# 14_-_PWR_5V_3V3_2V5.net
KiCad netlist of a schematic drawn in Altium Designer
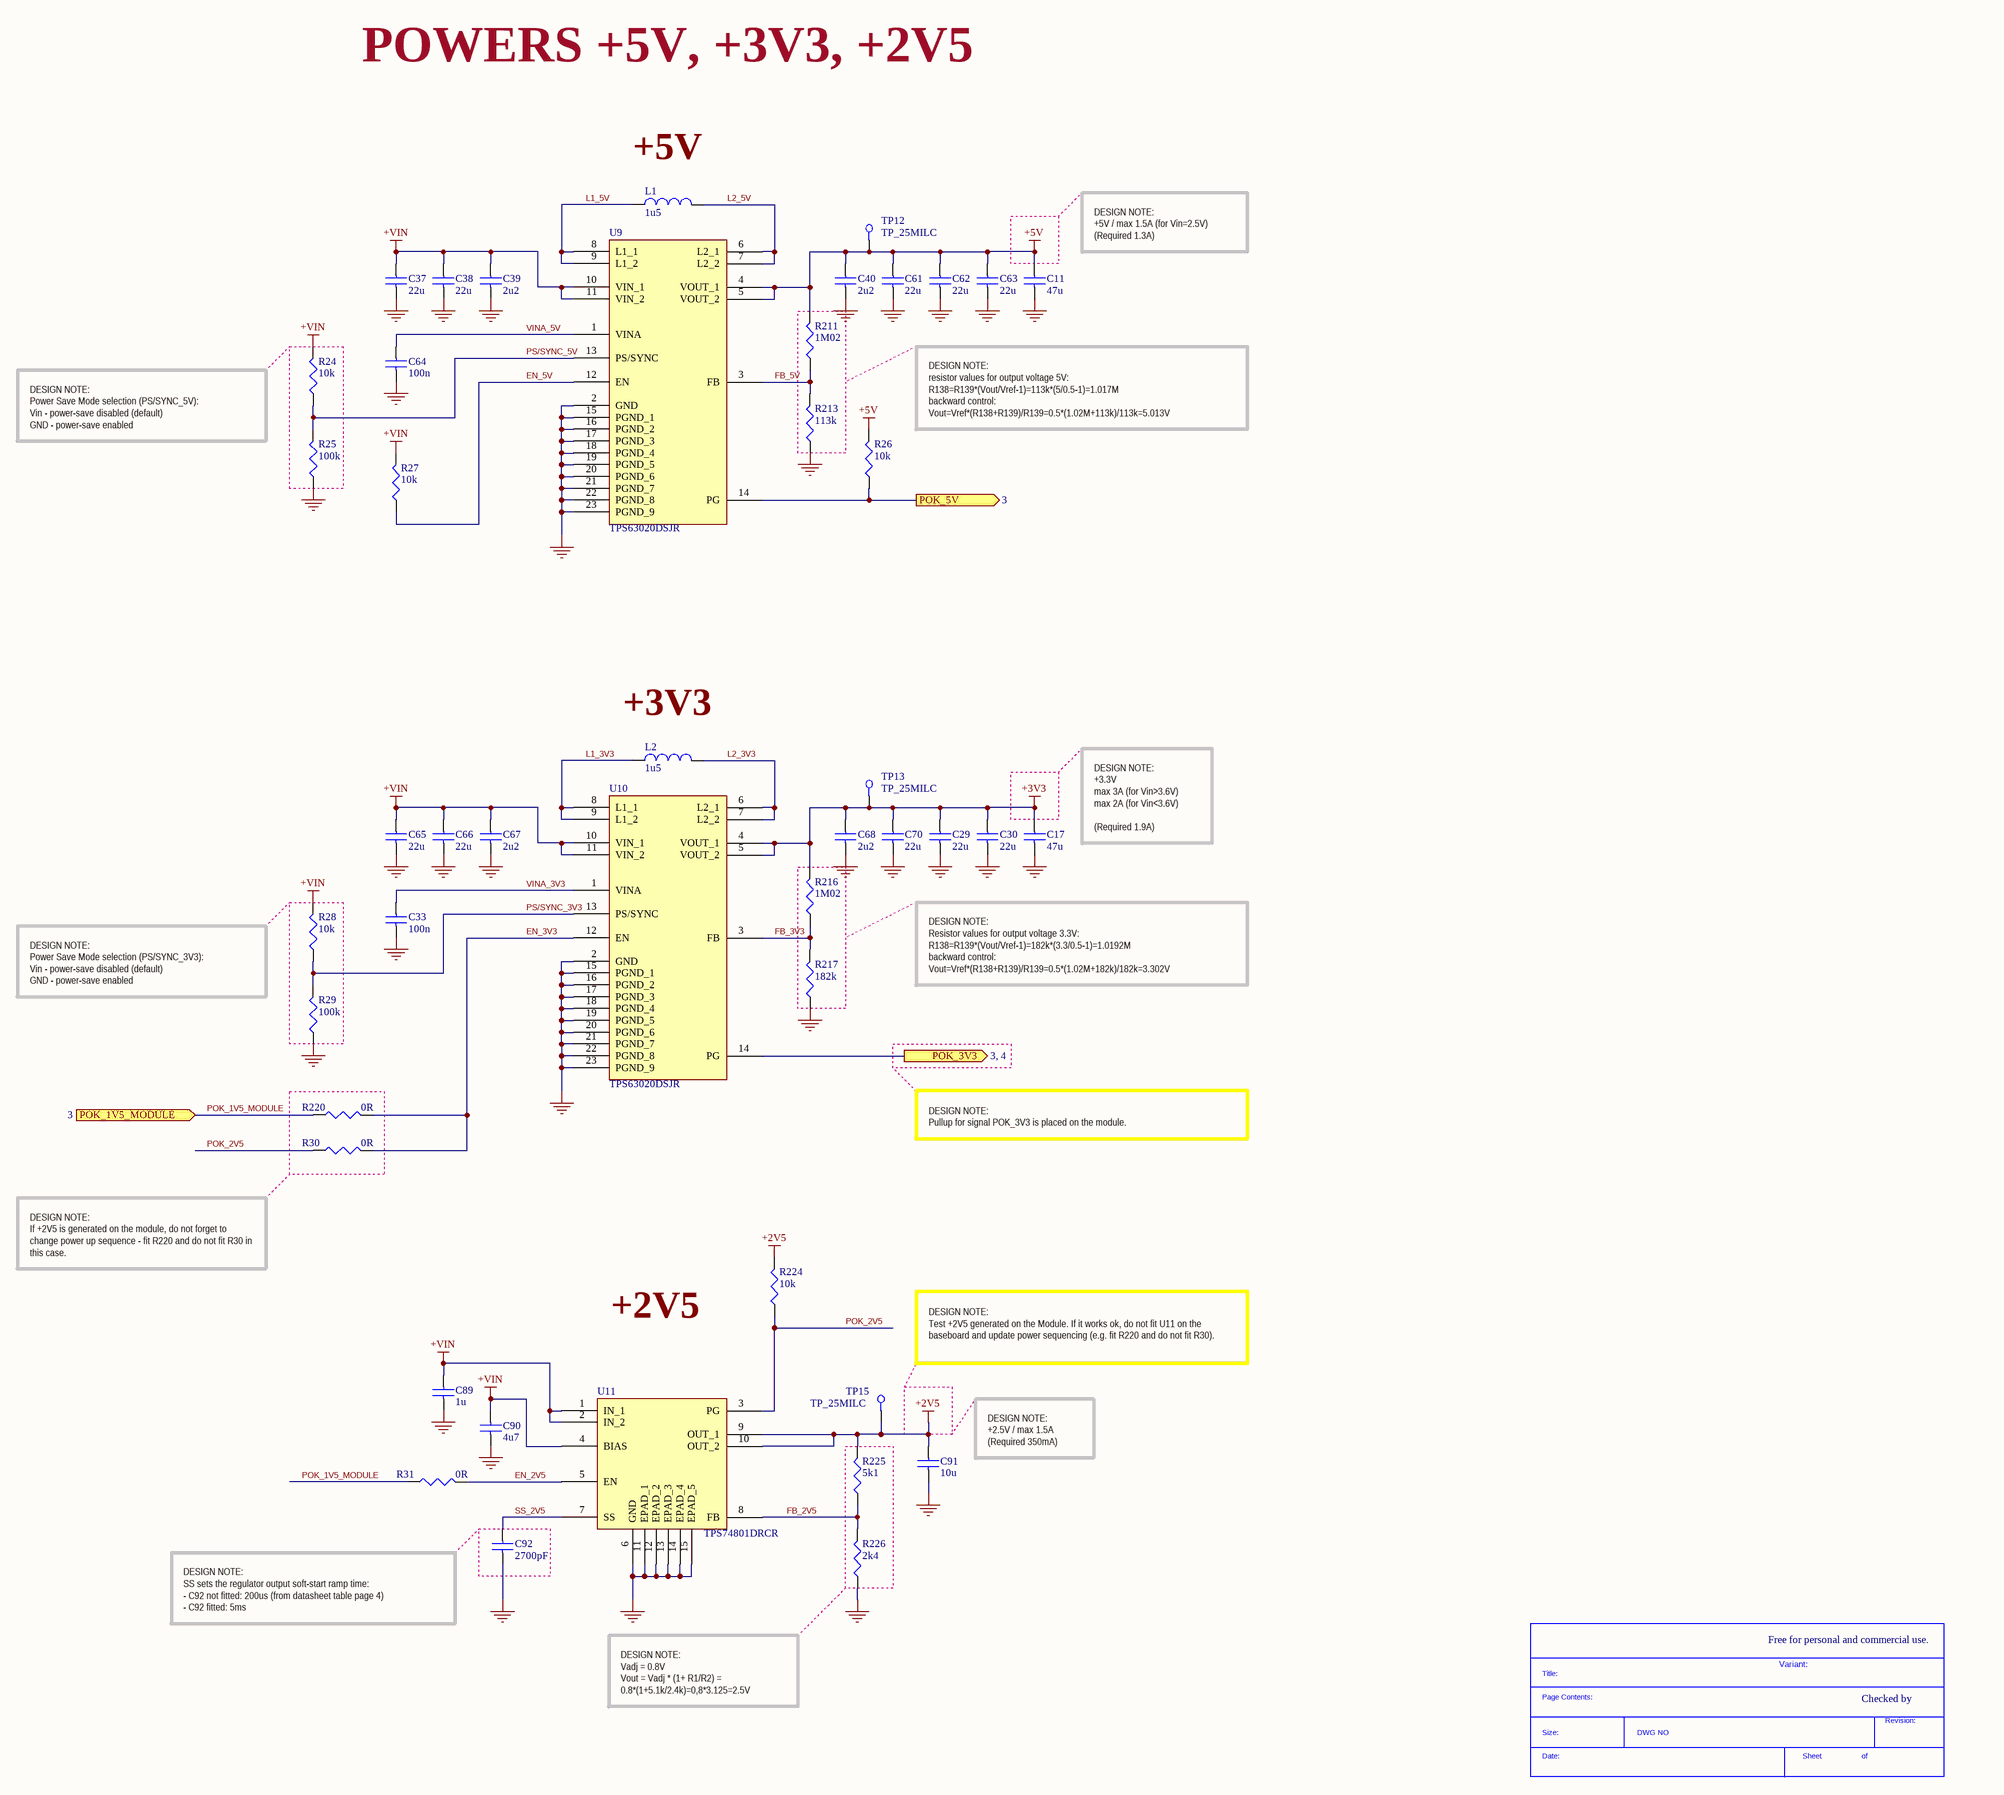
[diagram p0: [14] - PWR 5V, 3V3, 2V5.SchDoc]

(export (version "E")
  (design (tool "Eeschema 10.0.6"))
  (components
    (comp (ref "C11")
      (value "47u")
      (footprint "C0805")
      (description "CAP CER 47UF 6.3V 20% X5R 0805")
      (fields
        (field (name "MANUFACTURER") "Taiyo Yuden")
        (field (name "MANUFACTURER PART NUMBER") "JMK212BJ476MG-T")
        (field (name ".CREATOR") "MM")
        (field (name ".CHECKED SCH") "MM")
        (field (name ".CHECKED PCB") "MM")
      )
      (libsource (lib "Integrated_Library_FEDEVEL_APR_2015") (part "JMK212BJ476MG-T"))
    )
    (comp (ref "C17")
      (value "47u")
      (footprint "C0805")
      (description "CAP CER 47UF 6.3V 20% X5R 0805")
      (fields
        (field (name "MANUFACTURER") "Taiyo Yuden")
        (field (name "MANUFACTURER PART NUMBER") "JMK212BJ476MG-T")
        (field (name ".CREATOR") "MM")
        (field (name ".CHECKED SCH") "MM")
        (field (name ".CHECKED PCB") "MM")
      )
      (libsource (lib "Integrated_Library_FEDEVEL_APR_2015") (part "JMK212BJ476MG-T"))
    )
    (comp (ref "C29")
      (value "22u")
      (footprint "C0603")
      (description "CAP CER 22UF 6.3V 20% X5R 0603")
      (fields
        (field (name "MANUFACTURER") "TDK Corporation")
        (field (name "MANUFACTURER PART NUMBER") "C1608X5R0J226M080AC")
        (field (name ".CREATOR") "MM")
        (field (name ".CHECKED PCB") "MM")
        (field (name ".CHECKED SCH") "MM")
      )
      (libsource (lib "Integrated_Library_FEDEVEL_APR_2015") (part "C1608X5R0J226M080AC"))
    )
    (comp (ref "C30")
      (value "22u")
      (footprint "C0603")
      (description "CAP CER 22UF 6.3V 20% X5R 0603")
      (fields
        (field (name "MANUFACTURER") "TDK Corporation")
        (field (name "MANUFACTURER PART NUMBER") "C1608X5R0J226M080AC")
        (field (name ".CREATOR") "MM")
        (field (name ".CHECKED PCB") "MM")
        (field (name ".CHECKED SCH") "MM")
      )
      (libsource (lib "Integrated_Library_FEDEVEL_APR_2015") (part "C1608X5R0J226M080AC"))
    )
    (comp (ref "C33")
      (value "100n")
      (footprint "C0402")
      (description "CAP CER .10UF 50V X5R 10% 0402")
      (fields
        (field (name "MANUFACTURER") "TDK Corporation")
        (field (name "MANUFACTURER PART NUMBER") "C1005X5R1H104K")
      )
      (libsource (lib "Integrated_Library_FEDEVEL_APR_2015") (part "C1005X5R1H104K"))
    )
    (comp (ref "C37")
      (value "22u")
      (footprint "C0603")
      (description "CAP CER 22UF 6.3V 20% X5R 0603")
      (fields
        (field (name "MANUFACTURER") "TDK Corporation")
        (field (name "MANUFACTURER PART NUMBER") "C1608X5R0J226M080AC")
        (field (name ".CREATOR") "MM")
        (field (name ".CHECKED PCB") "MM")
        (field (name ".CHECKED SCH") "MM")
      )
      (libsource (lib "Integrated_Library_FEDEVEL_APR_2015") (part "C1608X5R0J226M080AC"))
    )
    (comp (ref "C38")
      (value "22u")
      (footprint "C0603")
      (description "CAP CER 22UF 6.3V 20% X5R 0603")
      (fields
        (field (name "MANUFACTURER") "TDK Corporation")
        (field (name "MANUFACTURER PART NUMBER") "C1608X5R0J226M080AC")
        (field (name ".CREATOR") "MM")
        (field (name ".CHECKED PCB") "MM")
        (field (name ".CHECKED SCH") "MM")
      )
      (libsource (lib "Integrated_Library_FEDEVEL_APR_2015") (part "C1608X5R0J226M080AC"))
    )
    (comp (ref "C39")
      (value "2u2")
      (footprint "C0402")
      (description "CAP CER 2.2UF 10V 10% X5R 0402")
      (fields
        (field (name "MANUFACTURER") "TDK Corporation")
        (field (name "MANUFACTURER PART NUMBER") "C1005X5R1A225K")
      )
      (libsource (lib "Integrated_Library_FEDEVEL_APR_2015") (part "C1005X5R1A225K"))
    )
    (comp (ref "C40")
      (value "2u2")
      (footprint "C0402")
      (description "CAP CER 2.2UF 10V 10% X5R 0402")
      (fields
        (field (name "MANUFACTURER") "TDK Corporation")
        (field (name "MANUFACTURER PART NUMBER") "C1005X5R1A225K")
      )
      (libsource (lib "Integrated_Library_FEDEVEL_APR_2015") (part "C1005X5R1A225K"))
    )
    (comp (ref "C61")
      (value "22u")
      (footprint "C0603")
      (description "CAP CER 22UF 6.3V 20% X5R 0603")
      (fields
        (field (name "MANUFACTURER") "TDK Corporation")
        (field (name "MANUFACTURER PART NUMBER") "C1608X5R0J226M080AC")
        (field (name ".CREATOR") "MM")
        (field (name ".CHECKED PCB") "MM")
        (field (name ".CHECKED SCH") "MM")
      )
      (libsource (lib "Integrated_Library_FEDEVEL_APR_2015") (part "C1608X5R0J226M080AC"))
    )
    (comp (ref "C62")
      (value "22u")
      (footprint "C0603")
      (description "CAP CER 22UF 6.3V 20% X5R 0603")
      (fields
        (field (name "MANUFACTURER") "TDK Corporation")
        (field (name "MANUFACTURER PART NUMBER") "C1608X5R0J226M080AC")
        (field (name ".CREATOR") "MM")
        (field (name ".CHECKED PCB") "MM")
        (field (name ".CHECKED SCH") "MM")
      )
      (libsource (lib "Integrated_Library_FEDEVEL_APR_2015") (part "C1608X5R0J226M080AC"))
    )
    (comp (ref "C63")
      (value "22u")
      (footprint "C0603")
      (description "CAP CER 22UF 6.3V 20% X5R 0603")
      (fields
        (field (name "MANUFACTURER") "TDK Corporation")
        (field (name "MANUFACTURER PART NUMBER") "C1608X5R0J226M080AC")
        (field (name ".CREATOR") "MM")
        (field (name ".CHECKED PCB") "MM")
        (field (name ".CHECKED SCH") "MM")
      )
      (libsource (lib "Integrated_Library_FEDEVEL_APR_2015") (part "C1608X5R0J226M080AC"))
    )
    (comp (ref "C64")
      (value "100n")
      (footprint "C0402")
      (description "CAP CER .10UF 50V X5R 10% 0402")
      (fields
        (field (name "MANUFACTURER") "TDK Corporation")
        (field (name "MANUFACTURER PART NUMBER") "C1005X5R1H104K")
      )
      (libsource (lib "Integrated_Library_FEDEVEL_APR_2015") (part "C1005X5R1H104K"))
    )
    (comp (ref "C65")
      (value "22u")
      (footprint "C0603")
      (description "CAP CER 22UF 6.3V 20% X5R 0603")
      (fields
        (field (name "MANUFACTURER") "TDK Corporation")
        (field (name "MANUFACTURER PART NUMBER") "C1608X5R0J226M080AC")
        (field (name ".CREATOR") "MM")
        (field (name ".CHECKED PCB") "MM")
        (field (name ".CHECKED SCH") "MM")
      )
      (libsource (lib "Integrated_Library_FEDEVEL_APR_2015") (part "C1608X5R0J226M080AC"))
    )
    (comp (ref "C66")
      (value "22u")
      (footprint "C0603")
      (description "CAP CER 22UF 6.3V 20% X5R 0603")
      (fields
        (field (name "MANUFACTURER") "TDK Corporation")
        (field (name "MANUFACTURER PART NUMBER") "C1608X5R0J226M080AC")
        (field (name ".CREATOR") "MM")
        (field (name ".CHECKED PCB") "MM")
        (field (name ".CHECKED SCH") "MM")
      )
      (libsource (lib "Integrated_Library_FEDEVEL_APR_2015") (part "C1608X5R0J226M080AC"))
    )
    (comp (ref "C67")
      (value "2u2")
      (footprint "C0402")
      (description "CAP CER 2.2UF 10V 10% X5R 0402")
      (fields
        (field (name "MANUFACTURER") "TDK Corporation")
        (field (name "MANUFACTURER PART NUMBER") "C1005X5R1A225K")
      )
      (libsource (lib "Integrated_Library_FEDEVEL_APR_2015") (part "C1005X5R1A225K"))
    )
    (comp (ref "C68")
      (value "2u2")
      (footprint "C0402")
      (description "CAP CER 2.2UF 10V 10% X5R 0402")
      (fields
        (field (name "MANUFACTURER") "TDK Corporation")
        (field (name "MANUFACTURER PART NUMBER") "C1005X5R1A225K")
      )
      (libsource (lib "Integrated_Library_FEDEVEL_APR_2015") (part "C1005X5R1A225K"))
    )
    (comp (ref "C70")
      (value "22u")
      (footprint "C0603")
      (description "CAP CER 22UF 6.3V 20% X5R 0603")
      (fields
        (field (name "MANUFACTURER") "TDK Corporation")
        (field (name "MANUFACTURER PART NUMBER") "C1608X5R0J226M080AC")
        (field (name ".CREATOR") "MM")
        (field (name ".CHECKED PCB") "MM")
        (field (name ".CHECKED SCH") "MM")
      )
      (libsource (lib "Integrated_Library_FEDEVEL_APR_2015") (part "C1608X5R0J226M080AC"))
    )
    (comp (ref "C89")
      (value "1u")
      (footprint "C0402")
      (description "CAP CER 1.0UF 16V X5R 0402")
      (fields
        (field (name "MANUFACTURER") "TDK Corporation")
        (field (name "MANUFACTURER PART NUMBER") "C1005X5R1C105K")
      )
      (libsource (lib "Integrated_Library_FEDEVEL_APR_2015") (part "C1005X5R1C105K"))
    )
    (comp (ref "C90")
      (value "4u7")
      (footprint "C0402")
      (description "CAP CER 4.7UF 10V 20% X5R 0402")
      (fields
        (field (name "MANUFACTURER") "TDK Corporation")
        (field (name "MANUFACTURER PART NUMBER") "C1005X5R1A475M")
      )
      (libsource (lib "Integrated_Library_FEDEVEL_APR_2015") (part "C1005X5R1A475M"))
    )
    (comp (ref "C91")
      (value "10u")
      (footprint "C0603")
      (description "CAP CER 10UF 6.3V X5R 20% 0603")
      (fields
        (field (name "MANUFACTURER") "TDK Corporation")
        (field (name "MANUFACTURER PART NUMBER") "C1608X5R0J106M")
      )
      (libsource (lib "Integrated_Library_FEDEVEL_APR_2015") (part "C1608X5R0J106M"))
    )
    (comp (ref "C92")
      (value "2700pF")
      (footprint "C0402")
      (description "CAP CER 2700PF 50V 10% X7R 0402")
      (fields
        (field (name "MANUFACTURER") "Murata Electronics North America")
        (field (name "MANUFACTURER PART NUMBER") "GRM155R71H272KA01D")
      )
      (libsource (lib "Integrated_Library_FEDEVEL_APR_2015") (part "GRM155R71H272KA01D"))
    )
    (comp (ref "L1")
      (value "1u5")
      (footprint "IHLP_204MILX216MIL")
      (description "FIXED IND 1.5UH 7.5A 18.5 MOHM")
      (fields
        (field (name "MANUFACTURER") "Vishay Dale")
        (field (name "MANUFACTURER PART NUMBER") "IHLP2020CZER1R5M11")
        (field (name ".CREATOR") "MM")
        (field (name ".CHECKED PCB") "MM")
        (field (name ".CHECKED SCH") "MM")
      )
      (libsource (lib "Integrated_Library_FEDEVEL_APR_2015") (part "IHLP2020CZER1R5M11"))
    )
    (comp (ref "L2")
      (value "1u5")
      (footprint "IHLP_204MILX216MIL")
      (description "FIXED IND 1.5UH 7.5A 18.5 MOHM")
      (fields
        (field (name "MANUFACTURER") "Vishay Dale")
        (field (name "MANUFACTURER PART NUMBER") "IHLP2020CZER1R5M11")
        (field (name ".CREATOR") "MM")
        (field (name ".CHECKED PCB") "MM")
        (field (name ".CHECKED SCH") "MM")
      )
      (libsource (lib "Integrated_Library_FEDEVEL_APR_2015") (part "IHLP2020CZER1R5M11"))
    )
    (comp (ref "R24")
      (value "10k")
      (footprint "R0402")
      (description "RES 10.0K OHM 1/16W 1% 0402 SMD")
      (fields
        (field (name "MANUFACTURER") "Yageo")
        (field (name "MANUFACTURER PART NUMBER") "RC0402FR-0710KL")
      )
      (libsource (lib "Integrated_Library_FEDEVEL_APR_2015") (part "RC0402FR-0710KL"))
    )
    (comp (ref "R25")
      (value "100k")
      (footprint "R0402")
      (description "RES 100K OHM 1/16W 1% 0402 SMD")
      (fields
        (field (name "MANUFACTURER") "Stackpole Electronics Inc")
        (field (name "MANUFACTURER PART NUMBER") "RMCF0402FT100K")
      )
      (libsource (lib "Integrated_Library_FEDEVEL_APR_2015") (part "RMCF0402FT100K"))
    )
    (comp (ref "R26")
      (value "10k")
      (footprint "R0402")
      (description "RES 10.0K OHM 1/16W 1% 0402 SMD")
      (fields
        (field (name "MANUFACTURER") "Yageo")
        (field (name "MANUFACTURER PART NUMBER") "RC0402FR-0710KL")
      )
      (libsource (lib "Integrated_Library_FEDEVEL_APR_2015") (part "RC0402FR-0710KL"))
    )
    (comp (ref "R27")
      (value "10k")
      (footprint "R0402")
      (description "RES 10.0K OHM 1/16W 1% 0402 SMD")
      (fields
        (field (name "MANUFACTURER") "Yageo")
        (field (name "MANUFACTURER PART NUMBER") "RC0402FR-0710KL")
      )
      (libsource (lib "Integrated_Library_FEDEVEL_APR_2015") (part "RC0402FR-0710KL"))
    )
    (comp (ref "R28")
      (value "10k")
      (footprint "R0402")
      (description "RES 10.0K OHM 1/16W 1% 0402 SMD")
      (fields
        (field (name "MANUFACTURER") "Yageo")
        (field (name "MANUFACTURER PART NUMBER") "RC0402FR-0710KL")
      )
      (libsource (lib "Integrated_Library_FEDEVEL_APR_2015") (part "RC0402FR-0710KL"))
    )
    (comp (ref "R29")
      (value "100k")
      (footprint "R0402")
      (description "RES 100K OHM 1/16W 1% 0402 SMD")
      (fields
        (field (name "MANUFACTURER") "Stackpole Electronics Inc")
        (field (name "MANUFACTURER PART NUMBER") "RMCF0402FT100K")
      )
      (libsource (lib "Integrated_Library_FEDEVEL_APR_2015") (part "RMCF0402FT100K"))
    )
    (comp (ref "R30")
      (value "0R")
      (footprint "R0402")
      (description "RES 0.0 OHM 1/16W 0402 SMD")
      (fields
        (field (name "MANUFACTURER") "Yageo")
        (field (name "MANUFACTURER PART NUMBER") "RC0402JR-070RL")
      )
      (libsource (lib "Integrated_Library_FEDEVEL_APR_2015") (part "RC0402JR-070RL"))
    )
    (comp (ref "R31")
      (value "0R")
      (footprint "R0402")
      (description "RES 0.0 OHM 1/16W 0402 SMD")
      (fields
        (field (name "MANUFACTURER") "Yageo")
        (field (name "MANUFACTURER PART NUMBER") "RC0402JR-070RL")
      )
      (libsource (lib "Integrated_Library_FEDEVEL_APR_2015") (part "RC0402JR-070RL"))
    )
    (comp (ref "R211")
      (value "1M02")
      (footprint "R0402")
      (description "RES 1.02M OHM 1/16W 1% 0402 SMD")
      (fields
        (field (name "MANUFACTURER") "Vishay Dale")
        (field (name "MANUFACTURER PART NUMBER") "CRCW04021M02FKED")
        (field (name ".CREATOR") "MM")
        (field (name ".CHECKED PCB") "MM")
        (field (name ".CHECKED SCH") "MM")
      )
      (libsource (lib "Integrated_Library_FEDEVEL_APR_2015") (part "CRCW04021M02FKED"))
    )
    (comp (ref "R213")
      (value "113k")
      (footprint "R0402")
      (description "RES 113K OHM 1/16W 1% 0402 SMD")
      (fields
        (field (name "MANUFACTURER") "Vishay Dale")
        (field (name "MANUFACTURER PART NUMBER") "CRCW0402113KFKED")
        (field (name ".CREATOR") "MM")
        (field (name ".CHECKED PCB") "MM")
        (field (name ".CHECKED SCH") "MM")
      )
      (libsource (lib "Integrated_Library_FEDEVEL_APR_2015") (part "CRCW0402113KFKED"))
    )
    (comp (ref "R216")
      (value "1M02")
      (footprint "R0402")
      (description "RES 1.02M OHM 1/16W 1% 0402 SMD")
      (fields
        (field (name "MANUFACTURER") "Vishay Dale")
        (field (name "MANUFACTURER PART NUMBER") "CRCW04021M02FKED")
        (field (name ".CREATOR") "MM")
        (field (name ".CHECKED PCB") "MM")
        (field (name ".CHECKED SCH") "MM")
      )
      (libsource (lib "Integrated_Library_FEDEVEL_APR_2015") (part "CRCW04021M02FKED"))
    )
    (comp (ref "R217")
      (value "182k")
      (footprint "R0402")
      (description "RES 182K OHM 1/16W 1% 0402 SMD")
      (fields
        (field (name "MANUFACTURER") "Vishay Dale")
        (field (name "MANUFACTURER PART NUMBER") "CRCW0402182KFKED")
        (field (name ".CREATOR") "MM")
        (field (name ".CHECKED PCB") "MM")
        (field (name ".CHECKED SCH") "MM")
      )
      (libsource (lib "Integrated_Library_FEDEVEL_APR_2015") (part "CRCW0402182KFKED"))
    )
    (comp (ref "R220")
      (value "0R")
      (footprint "R0402")
      (description "RES 0.0 OHM 1/16W 0402 SMD")
      (fields
        (field (name "MANUFACTURER") "Yageo")
        (field (name "MANUFACTURER PART NUMBER") "RC0402JR-070RL")
      )
      (libsource (lib "Integrated_Library_FEDEVEL_APR_2015") (part "RC0402JR-070RL"))
    )
    (comp (ref "R224")
      (value "10k")
      (footprint "R0402")
      (description "RES 10.0K OHM 1/16W 1% 0402 SMD")
      (fields
        (field (name "MANUFACTURER") "Yageo")
        (field (name "MANUFACTURER PART NUMBER") "RC0402FR-0710KL")
      )
      (libsource (lib "Integrated_Library_FEDEVEL_APR_2015") (part "RC0402FR-0710KL"))
    )
    (comp (ref "R225")
      (value "5k1")
      (footprint "R0402")
      (description "RES 5.10K OHM 1/16W 1% 0402 SMD")
      (fields
        (field (name "MANUFACTURER") "Yageo")
        (field (name "MANUFACTURER PART NUMBER") "RC0402FR-075K1L")
        (field (name ".CHECKED PCB") "RF")
        (field (name ".CHECKED SCH") "RF")
      )
      (libsource (lib "Integrated_Library_FEDEVEL_APR_2015") (part "RC0402FR-075K1L"))
    )
    (comp (ref "R226")
      (value "2k4")
      (footprint "R0402")
      (description "RES 2.40K OHM 1/16W 1% 0402 SMD")
      (fields
        (field (name "MANUFACTURER") "Vishay Dale")
        (field (name "MANUFACTURER PART NUMBER") "CRCW04022K40FKED")
      )
      (libsource (lib "Integrated_Library_FEDEVEL_APR_2015") (part "CRCW04022K40FKED"))
    )
    (comp (ref "TP12")
      (value "TP_25MILC")
      (footprint "TP_25C")
      (description "Test Point 25mil")
      (libsource (lib "Integrated_Library_FEDEVEL_APR_2015") (part "TP_25MILC"))
    )
    (comp (ref "TP13")
      (value "TP_25MILC")
      (footprint "TP_25C")
      (description "Test Point 25mil")
      (libsource (lib "Integrated_Library_FEDEVEL_APR_2015") (part "TP_25MILC"))
    )
    (comp (ref "TP15")
      (value "TP_25MILC")
      (footprint "TP_25C")
      (description "Test Point 25mil")
      (libsource (lib "Integrated_Library_FEDEVEL_APR_2015") (part "TP_25MILC"))
    )
    (comp (ref "U9")
      (value "TPS63020DSJR")
      (footprint "DSJ (R-PVSON-N14)")
      (description "IC REG BUCK BST SYNC ADJ 14VSON")
      (fields
        (field (name "MANUFACTURER") "Texas Instruments")
        (field (name ".CREATOR") "MM")
        (field (name ".CHECKED PCB") "MM")
        (field (name ".CHECKED SCH") "MM")
      )
      (libsource (lib "Integrated_Library_FEDEVEL_APR_2015") (part "TPS63020DSJR"))
    )
    (comp (ref "U10")
      (value "TPS63020DSJR")
      (footprint "DSJ (R-PVSON-N14)")
      (description "IC REG BUCK BST SYNC ADJ 14VSON")
      (fields
        (field (name "MANUFACTURER") "Texas Instruments")
        (field (name ".CREATOR") "MM")
        (field (name ".CHECKED PCB") "MM")
        (field (name ".CHECKED SCH") "MM")
      )
      (libsource (lib "Integrated_Library_FEDEVEL_APR_2015") (part "TPS63020DSJR"))
    )
    (comp (ref "U11")
      (value "TPS74801DRCR")
      (footprint "DRC (S-PVSON-N10)")
      (description "IC REG LDO ADJ 1.5A 10SON")
      (fields (field (name "MANUFACTURER") "Texas Instruments") (field (name ".CREATOR") "MM"))
      (libsource (lib "Integrated_Library_FEDEVEL_APR_2015") (part "TPS74801DRCR"))
    )
  )
  (nets
    (net (code "1") (name "+2V5") (class "Default")
      (node (ref "C91") (pin "1") (pinfunction "1_1") (pintype "passive"))
      (node (ref "R224") (pin "2") (pinfunction "2_2") (pintype "passive"))
      (node (ref "R225") (pin "2") (pinfunction "2_2") (pintype "passive"))
      (node (ref "TP15") (pin "1") (pinfunction "1_1") (pintype "passive"))
      (node (ref "U11") (pin "10") (pinfunction "OUT_2_10") (pintype "passive"))
      (node (ref "U11") (pin "9") (pinfunction "OUT_1_9") (pintype "passive"))
    )
    (net (code "2") (name "+3V3") (class "Default")
      (node (ref "C17") (pin "1") (pinfunction "1_1") (pintype "passive"))
      (node (ref "C29") (pin "1") (pinfunction "1_1") (pintype "passive"))
      (node (ref "C30") (pin "1") (pinfunction "1_1") (pintype "passive"))
      (node (ref "C68") (pin "1") (pinfunction "1_1") (pintype "passive"))
      (node (ref "C70") (pin "1") (pinfunction "1_1") (pintype "passive"))
      (node (ref "R216") (pin "2") (pinfunction "2_2") (pintype "passive"))
      (node (ref "TP13") (pin "1") (pinfunction "1_1") (pintype "passive"))
      (node (ref "U10") (pin "4") (pinfunction "VOUT_1_4") (pintype "passive"))
      (node (ref "U10") (pin "5") (pinfunction "VOUT_2_5") (pintype "passive"))
    )
    (net (code "3") (name "+5V") (class "Default")
      (node (ref "C11") (pin "1") (pinfunction "1_1") (pintype "passive"))
      (node (ref "C40") (pin "1") (pinfunction "1_1") (pintype "passive"))
      (node (ref "C61") (pin "1") (pinfunction "1_1") (pintype "passive"))
      (node (ref "C62") (pin "1") (pinfunction "1_1") (pintype "passive"))
      (node (ref "C63") (pin "1") (pinfunction "1_1") (pintype "passive"))
      (node (ref "R211") (pin "2") (pinfunction "2_2") (pintype "passive"))
      (node (ref "R26") (pin "2") (pinfunction "2_2") (pintype "passive"))
      (node (ref "TP12") (pin "1") (pinfunction "1_1") (pintype "passive"))
      (node (ref "U9") (pin "4") (pinfunction "VOUT_1_4") (pintype "passive"))
      (node (ref "U9") (pin "5") (pinfunction "VOUT_2_5") (pintype "passive"))
    )
    (net (code "4") (name "+VIN") (class "Default")
      (node (ref "C37") (pin "1") (pinfunction "1_1") (pintype "passive"))
      (node (ref "C38") (pin "1") (pinfunction "1_1") (pintype "passive"))
      (node (ref "C39") (pin "1") (pinfunction "1_1") (pintype "passive"))
      (node (ref "C65") (pin "1") (pinfunction "1_1") (pintype "passive"))
      (node (ref "C66") (pin "1") (pinfunction "1_1") (pintype "passive"))
      (node (ref "C67") (pin "1") (pinfunction "1_1") (pintype "passive"))
      (node (ref "C89") (pin "1") (pinfunction "1_1") (pintype "passive"))
      (node (ref "C90") (pin "1") (pinfunction "1_1") (pintype "passive"))
      (node (ref "R24") (pin "2") (pinfunction "2_2") (pintype "passive"))
      (node (ref "R27") (pin "2") (pinfunction "2_2") (pintype "passive"))
      (node (ref "R28") (pin "2") (pinfunction "2_2") (pintype "passive"))
      (node (ref "U10") (pin "10") (pinfunction "VIN_1_10") (pintype "passive"))
      (node (ref "U10") (pin "11") (pinfunction "VIN_2_11") (pintype "passive"))
      (node (ref "U11") (pin "1") (pinfunction "IN_1_1") (pintype "passive"))
      (node (ref "U11") (pin "2") (pinfunction "IN_2_2") (pintype "passive"))
      (node (ref "U11") (pin "4") (pinfunction "BIAS_4") (pintype "passive"))
      (node (ref "U9") (pin "10") (pinfunction "VIN_1_10") (pintype "passive"))
      (node (ref "U9") (pin "11") (pinfunction "VIN_2_11") (pintype "passive"))
    )
    (net (code "5") (name "/EN_2V5") (class "Default")
      (node (ref "R31") (pin "2") (pinfunction "2_2") (pintype "passive"))
      (node (ref "U11") (pin "5") (pinfunction "EN_5") (pintype "passive"))
    )
    (net (code "6") (name "/EN_3V3") (class "Default")
      (node (ref "R220") (pin "2") (pinfunction "2_2") (pintype "passive"))
      (node (ref "R30") (pin "2") (pinfunction "2_2") (pintype "passive"))
      (node (ref "U10") (pin "12") (pinfunction "EN_12") (pintype "passive"))
    )
    (net (code "7") (name "/EN_5V") (class "Default")
      (node (ref "R27") (pin "1") (pinfunction "1_1") (pintype "passive"))
      (node (ref "U9") (pin "12") (pinfunction "EN_12") (pintype "passive"))
    )
    (net (code "8") (name "/FB_2V5") (class "Default")
      (node (ref "R225") (pin "1") (pinfunction "1_1") (pintype "passive"))
      (node (ref "R226") (pin "2") (pinfunction "2_2") (pintype "passive"))
      (node (ref "U11") (pin "8") (pinfunction "FB_8") (pintype "passive"))
    )
    (net (code "9") (name "/FB_3V3") (class "Default")
      (node (ref "R216") (pin "1") (pinfunction "1_1") (pintype "passive"))
      (node (ref "R217") (pin "2") (pinfunction "2_2") (pintype "passive"))
      (node (ref "U10") (pin "3") (pinfunction "FB_3") (pintype "passive"))
    )
    (net (code "10") (name "/FB_5V") (class "Default")
      (node (ref "R211") (pin "1") (pinfunction "1_1") (pintype "passive"))
      (node (ref "R213") (pin "2") (pinfunction "2_2") (pintype "passive"))
      (node (ref "U9") (pin "3") (pinfunction "FB_3") (pintype "passive"))
    )
    (net (code "11") (name "/L1_3V3") (class "Default")
      (node (ref "L2") (pin "1") (pinfunction "1_1") (pintype "passive"))
      (node (ref "U10") (pin "8") (pinfunction "L1_1_8") (pintype "passive"))
      (node (ref "U10") (pin "9") (pinfunction "L1_2_9") (pintype "passive"))
    )
    (net (code "12") (name "/L1_5V") (class "Default")
      (node (ref "L1") (pin "1") (pinfunction "1_1") (pintype "passive"))
      (node (ref "U9") (pin "8") (pinfunction "L1_1_8") (pintype "passive"))
      (node (ref "U9") (pin "9") (pinfunction "L1_2_9") (pintype "passive"))
    )
    (net (code "13") (name "/L2_3V3") (class "Default")
      (node (ref "L2") (pin "2") (pinfunction "2_2") (pintype "passive"))
      (node (ref "U10") (pin "6") (pinfunction "L2_1_6") (pintype "passive"))
      (node (ref "U10") (pin "7") (pinfunction "L2_2_7") (pintype "passive"))
    )
    (net (code "14") (name "/L2_5V") (class "Default")
      (node (ref "L1") (pin "2") (pinfunction "2_2") (pintype "passive"))
      (node (ref "U9") (pin "6") (pinfunction "L2_1_6") (pintype "passive"))
      (node (ref "U9") (pin "7") (pinfunction "L2_2_7") (pintype "passive"))
    )
    (net (code "15") (name "/POK_1V5_MODULE") (class "Default")
      (node (ref "R220") (pin "1") (pinfunction "1_1") (pintype "passive"))
      (node (ref "R31") (pin "1") (pinfunction "1_1") (pintype "passive"))
    )
    (net (code "16") (name "/POK_2V5") (class "Default")
      (node (ref "R224") (pin "1") (pinfunction "1_1") (pintype "passive"))
      (node (ref "R30") (pin "1") (pinfunction "1_1") (pintype "passive"))
      (node (ref "U11") (pin "3") (pinfunction "PG_3") (pintype "passive"))
    )
    (net (code "17") (name "/POK_3V3") (class "Default")
      (node (ref "U10") (pin "14") (pinfunction "PG_14") (pintype "passive"))
    )
    (net (code "18") (name "/POK_5V") (class "Default")
      (node (ref "R26") (pin "1") (pinfunction "1_1") (pintype "passive"))
      (node (ref "U9") (pin "14") (pinfunction "PG_14") (pintype "passive"))
    )
    (net (code "19") (name "/PS{slash}SYNC_3V3") (class "Default")
      (node (ref "R28") (pin "1") (pinfunction "1_1") (pintype "passive"))
      (node (ref "R29") (pin "2") (pinfunction "2_2") (pintype "passive"))
      (node (ref "U10") (pin "13") (pinfunction "PS/SYNC_13") (pintype "passive"))
    )
    (net (code "20") (name "/PS{slash}SYNC_5V") (class "Default")
      (node (ref "R24") (pin "1") (pinfunction "1_1") (pintype "passive"))
      (node (ref "R25") (pin "2") (pinfunction "2_2") (pintype "passive"))
      (node (ref "U9") (pin "13") (pinfunction "PS/SYNC_13") (pintype "passive"))
    )
    (net (code "21") (name "/SS_2V5") (class "Default")
      (node (ref "C92") (pin "1") (pinfunction "1_1") (pintype "passive"))
      (node (ref "U11") (pin "7") (pinfunction "SS_7") (pintype "passive"))
    )
    (net (code "22") (name "/VINA_3V3") (class "Default")
      (node (ref "C33") (pin "1") (pinfunction "1_1") (pintype "passive"))
      (node (ref "U10") (pin "1") (pinfunction "VINA_1") (pintype "passive"))
    )
    (net (code "23") (name "/VINA_5V") (class "Default")
      (node (ref "C64") (pin "1") (pinfunction "1_1") (pintype "passive"))
      (node (ref "U9") (pin "1") (pinfunction "VINA_1") (pintype "passive"))
    )
    (net (code "24") (name "GND") (class "Default")
      (node (ref "C11") (pin "2") (pinfunction "2_2") (pintype "passive"))
      (node (ref "C17") (pin "2") (pinfunction "2_2") (pintype "passive"))
      (node (ref "C29") (pin "2") (pinfunction "2_2") (pintype "passive"))
      (node (ref "C30") (pin "2") (pinfunction "2_2") (pintype "passive"))
      (node (ref "C33") (pin "2") (pinfunction "2_2") (pintype "passive"))
      (node (ref "C37") (pin "2") (pinfunction "2_2") (pintype "passive"))
      (node (ref "C38") (pin "2") (pinfunction "2_2") (pintype "passive"))
      (node (ref "C39") (pin "2") (pinfunction "2_2") (pintype "passive"))
      (node (ref "C40") (pin "2") (pinfunction "2_2") (pintype "passive"))
      (node (ref "C61") (pin "2") (pinfunction "2_2") (pintype "passive"))
      (node (ref "C62") (pin "2") (pinfunction "2_2") (pintype "passive"))
      (node (ref "C63") (pin "2") (pinfunction "2_2") (pintype "passive"))
      (node (ref "C64") (pin "2") (pinfunction "2_2") (pintype "passive"))
      (node (ref "C65") (pin "2") (pinfunction "2_2") (pintype "passive"))
      (node (ref "C66") (pin "2") (pinfunction "2_2") (pintype "passive"))
      (node (ref "C67") (pin "2") (pinfunction "2_2") (pintype "passive"))
      (node (ref "C68") (pin "2") (pinfunction "2_2") (pintype "passive"))
      (node (ref "C70") (pin "2") (pinfunction "2_2") (pintype "passive"))
      (node (ref "C89") (pin "2") (pinfunction "2_2") (pintype "passive"))
      (node (ref "C90") (pin "2") (pinfunction "2_2") (pintype "passive"))
      (node (ref "C91") (pin "2") (pinfunction "2_2") (pintype "passive"))
      (node (ref "C92") (pin "2") (pinfunction "2_2") (pintype "passive"))
      (node (ref "R213") (pin "1") (pinfunction "1_1") (pintype "passive"))
      (node (ref "R217") (pin "1") (pinfunction "1_1") (pintype "passive"))
      (node (ref "R226") (pin "1") (pinfunction "1_1") (pintype "passive"))
      (node (ref "R25") (pin "1") (pinfunction "1_1") (pintype "passive"))
      (node (ref "R29") (pin "1") (pinfunction "1_1") (pintype "passive"))
      (node (ref "U10") (pin "15") (pinfunction "PGND_1_15") (pintype "passive"))
      (node (ref "U10") (pin "16") (pinfunction "PGND_2_16") (pintype "passive"))
      (node (ref "U10") (pin "17") (pinfunction "PGND_3_17") (pintype "passive"))
      (node (ref "U10") (pin "18") (pinfunction "PGND_4_18") (pintype "passive"))
      (node (ref "U10") (pin "19") (pinfunction "PGND_5_19") (pintype "passive"))
      (node (ref "U10") (pin "2") (pinfunction "GND_2") (pintype "passive"))
      (node (ref "U10") (pin "20") (pinfunction "PGND_6_20") (pintype "passive"))
      (node (ref "U10") (pin "21") (pinfunction "PGND_7_21") (pintype "passive"))
      (node (ref "U10") (pin "22") (pinfunction "PGND_8_22") (pintype "passive"))
      (node (ref "U10") (pin "23") (pinfunction "PGND_9_23") (pintype "passive"))
      (node (ref "U11") (pin "11") (pinfunction "EPAD_1_11") (pintype "passive"))
      (node (ref "U11") (pin "12") (pinfunction "EPAD_2_12") (pintype "passive"))
      (node (ref "U11") (pin "13") (pinfunction "EPAD_3_13") (pintype "passive"))
      (node (ref "U11") (pin "14") (pinfunction "EPAD_4_14") (pintype "passive"))
      (node (ref "U11") (pin "15") (pinfunction "EPAD_5_15") (pintype "passive"))
      (node (ref "U11") (pin "6") (pinfunction "GND_6") (pintype "passive"))
      (node (ref "U9") (pin "15") (pinfunction "PGND_1_15") (pintype "passive"))
      (node (ref "U9") (pin "16") (pinfunction "PGND_2_16") (pintype "passive"))
      (node (ref "U9") (pin "17") (pinfunction "PGND_3_17") (pintype "passive"))
      (node (ref "U9") (pin "18") (pinfunction "PGND_4_18") (pintype "passive"))
      (node (ref "U9") (pin "19") (pinfunction "PGND_5_19") (pintype "passive"))
      (node (ref "U9") (pin "2") (pinfunction "GND_2") (pintype "passive"))
      (node (ref "U9") (pin "20") (pinfunction "PGND_6_20") (pintype "passive"))
      (node (ref "U9") (pin "21") (pinfunction "PGND_7_21") (pintype "passive"))
      (node (ref "U9") (pin "22") (pinfunction "PGND_8_22") (pintype "passive"))
      (node (ref "U9") (pin "23") (pinfunction "PGND_9_23") (pintype "passive"))
    )
  )
)
